# controller-c0m0.net
KiCad netlist of a schematic drawn in EAGLE
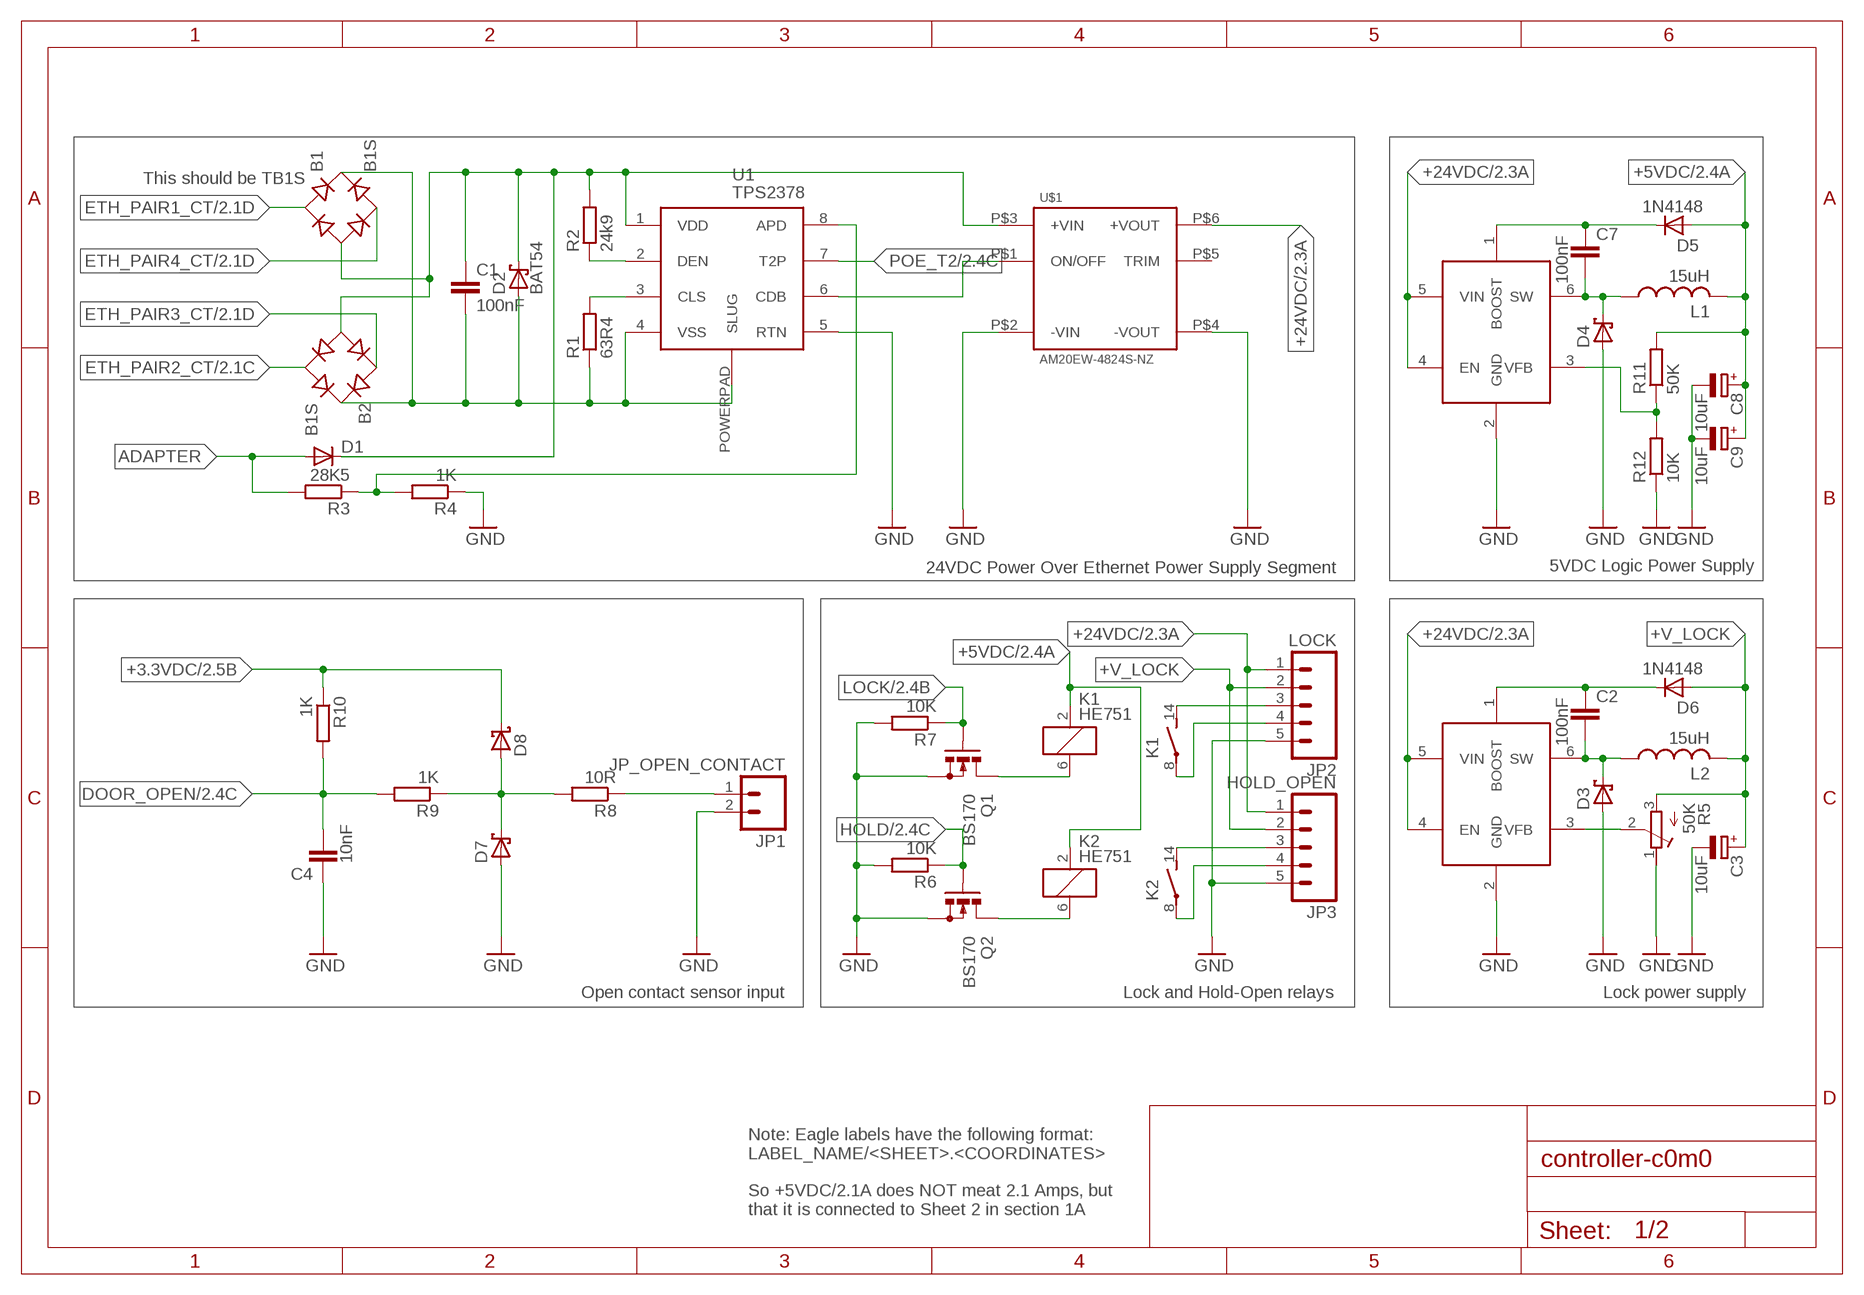
[diagram p0: schematic, sheet 1]
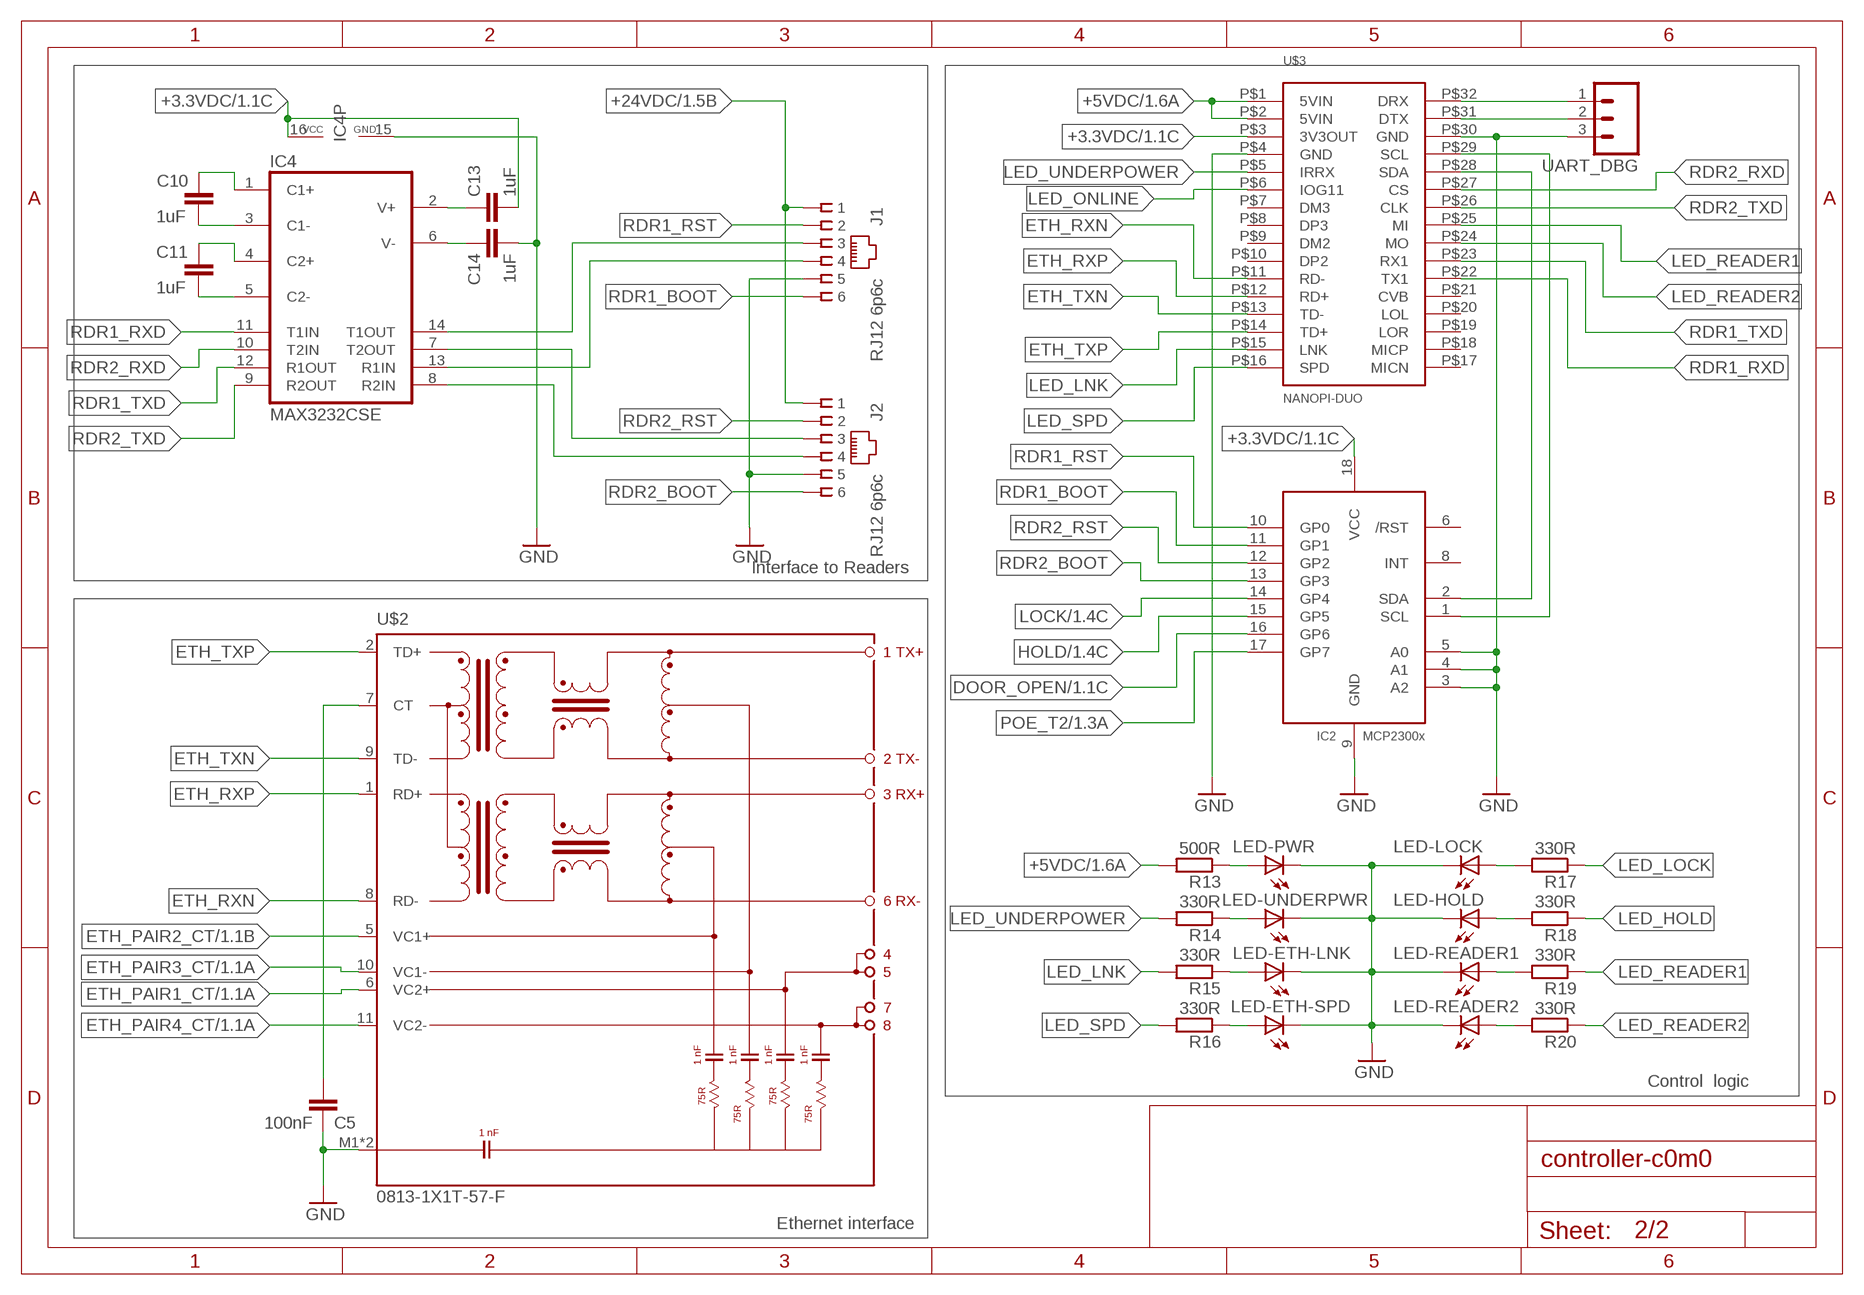
[diagram p1: schematic, sheet 2]

(export (version "E")
  (design (tool "Eeschema 10.0.6"))
  (components
    (comp (ref "C5")
      (value "100nF")
      (footprint "eagle-import:C0805")
      (libsource (lib "eagle-import") (part "C-EUC0805"))
    )
    (comp (ref "C10")
      (value "1uF")
      (footprint "eagle-import:C0805")
      (libsource (lib "eagle-import") (part "C-EUC0805"))
    )
    (comp (ref "C11")
      (value "1uF")
      (footprint "eagle-import:C0805")
      (libsource (lib "eagle-import") (part "C-EUC0805"))
    )
    (comp (ref "C13")
      (value "1uF")
      (footprint "eagle-import:C0805")
      (libsource (lib "eagle-import") (part "C-EUC0805"))
    )
    (comp (ref "C14")
      (value "1uF")
      (footprint "eagle-import:C0805")
      (libsource (lib "eagle-import") (part "C-EUC0805"))
    )
    (comp (ref "IC2")
      (value "MCP23008/SO")
      (footprint "eagle-import:SO18W")
      (libsource (lib "eagle-import") (part "MCP23008/SO"))
    )
    (comp (ref "IC4")
      (value "MAX3232CSE")
      (footprint "eagle-import:SO16")
      (libsource (lib "eagle-import") (part "MAX3232SEC"))
    )
    (comp (ref "J1")
      (value "RJ12 6p6c")
      (footprint "eagle-import:RJ11-NO_SHIELD")
      (libsource (lib "eagle-import") (part "RJ11-2X"))
    )
    (comp (ref "J2")
      (value "RJ12 6p6c")
      (footprint "eagle-import:RJ11-NO_SHIELD")
      (libsource (lib "eagle-import") (part "RJ11-2X"))
    )
    (comp (ref "LED-ETH-LNK")
      (value "LEDCHIP-LED0805")
      (footprint "eagle-import:CHIP-LED0805")
      (libsource (lib "eagle-import") (part "LEDCHIP-LED0805"))
    )
    (comp (ref "LED-ETH-SPD")
      (value "LEDCHIP-LED0805")
      (footprint "eagle-import:CHIP-LED0805")
      (libsource (lib "eagle-import") (part "LEDCHIP-LED0805"))
    )
    (comp (ref "LED-HOLD")
      (value "LEDCHIP-LED0805")
      (footprint "eagle-import:CHIP-LED0805")
      (libsource (lib "eagle-import") (part "LEDCHIP-LED0805"))
    )
    (comp (ref "LED-LOCK")
      (value "LEDCHIP-LED0805")
      (footprint "eagle-import:CHIP-LED0805")
      (libsource (lib "eagle-import") (part "LEDCHIP-LED0805"))
    )
    (comp (ref "LED-PWR")
      (value "LEDCHIP-LED0805")
      (footprint "eagle-import:CHIP-LED0805")
      (libsource (lib "eagle-import") (part "LEDCHIP-LED0805"))
    )
    (comp (ref "LED-READER1")
      (value "LEDCHIP-LED0805")
      (footprint "eagle-import:CHIP-LED0805")
      (libsource (lib "eagle-import") (part "LEDCHIP-LED0805"))
    )
    (comp (ref "LED-READER2")
      (value "LEDCHIP-LED0805")
      (footprint "eagle-import:CHIP-LED0805")
      (libsource (lib "eagle-import") (part "LEDCHIP-LED0805"))
    )
    (comp (ref "LED-UNDERPWR")
      (value "LEDCHIP-LED0805")
      (footprint "eagle-import:CHIP-LED0805")
      (libsource (lib "eagle-import") (part "LEDCHIP-LED0805"))
    )
    (comp (ref "R13")
      (value "500R")
      (footprint "eagle-import:R0805")
      (libsource (lib "eagle-import") (part "R"))
    )
    (comp (ref "R14")
      (value "330R")
      (footprint "eagle-import:R0805")
      (libsource (lib "eagle-import") (part "R"))
    )
    (comp (ref "R15")
      (value "330R")
      (footprint "eagle-import:R0805")
      (libsource (lib "eagle-import") (part "R"))
    )
    (comp (ref "R16")
      (value "330R")
      (footprint "eagle-import:R0805")
      (libsource (lib "eagle-import") (part "R"))
    )
    (comp (ref "R17")
      (value "330R")
      (footprint "eagle-import:R0805")
      (libsource (lib "eagle-import") (part "R"))
    )
    (comp (ref "R18")
      (value "330R")
      (footprint "eagle-import:R0805")
      (libsource (lib "eagle-import") (part "R"))
    )
    (comp (ref "R19")
      (value "330R")
      (footprint "eagle-import:R0805")
      (libsource (lib "eagle-import") (part "R"))
    )
    (comp (ref "R20")
      (value "330R")
      (footprint "eagle-import:R0805")
      (libsource (lib "eagle-import") (part "R"))
    )
    (comp (ref "U$2")
      (value "0813-1X1T-57-F")
      (footprint "eagle-import:J1")
      (libsource (lib "eagle-import") (part "0813-1X1T-57-F"))
    )
    (comp (ref "U$3")
      (value "NANOPI-DUO")
      (footprint "eagle-import:NANOPI-DUO")
      (libsource (lib "eagle-import") (part "NANOPI-DUO"))
    )
    (comp (ref "UART_DBG")
      (value "M03LONGPADS")
      (footprint "eagle-import:1X03_LONGPADS")
      (libsource (lib "eagle-import") (part "M03LONGPADS"))
    )
    (comp (ref "B1")
      (value "B1S")
      (footprint "eagle-import:MBS")
      (libsource (lib "eagle-import") (part "BS1"))
    )
    (comp (ref "B2")
      (value "B1S")
      (footprint "eagle-import:MBS")
      (libsource (lib "eagle-import") (part "BS1"))
    )
    (comp (ref "C1")
      (value "100nF")
      (footprint "eagle-import:C0805")
      (libsource (lib "eagle-import") (part "C"))
    )
    (comp (ref "C2")
      (value "100nF")
      (footprint "eagle-import:C0805")
      (libsource (lib "eagle-import") (part "C-EUC0805"))
    )
    (comp (ref "C3")
      (value "10uF")
      (footprint "eagle-import:A_3216-18R")
      (libsource (lib "eagle-import") (part "CPOL-EUA/3216-18R"))
    )
    (comp (ref "C4")
      (value "10nF")
      (footprint "eagle-import:C0805")
      (libsource (lib "eagle-import") (part "C-EUC0805"))
    )
    (comp (ref "C7")
      (value "100nF")
      (footprint "eagle-import:C0805")
      (libsource (lib "eagle-import") (part "C-EUC0805"))
    )
    (comp (ref "C8")
      (value "10uF")
      (footprint "eagle-import:A_3216-18R")
      (libsource (lib "eagle-import") (part "CPOL-EUA/3216-18R"))
    )
    (comp (ref "C9")
      (value "10uF")
      (footprint "eagle-import:A_3216-18R")
      (libsource (lib "eagle-import") (part "CPOL-EUA/3216-18R"))
    )
    (comp (ref "D1")
      (value "DIODE-SOD323-W")
      (footprint "eagle-import:SOD323-W")
      (libsource (lib "eagle-import") (part "diode_210_DIODE-SOD323-W"))
    )
    (comp (ref "D2")
      (value "BAT54")
      (footprint "eagle-import:SOT23")
      (libsource (lib "eagle-import") (part "BAT54"))
    )
    (comp (ref "D3")
      (value "BAT60J")
      (footprint "eagle-import:SOD323_ST")
      (libsource (lib "eagle-import") (part "BAT60J"))
    )
    (comp (ref "D4")
      (value "BAT60J")
      (footprint "eagle-import:SOD323_ST")
      (libsource (lib "eagle-import") (part "BAT60J"))
    )
    (comp (ref "D5")
      (value "1N4148")
      (footprint "eagle-import:SOD323-W")
      (libsource (lib "eagle-import") (part "DIODE-SOD323-W"))
    )
    (comp (ref "D6")
      (value "1N4148")
      (footprint "eagle-import:SOD323-W")
      (libsource (lib "eagle-import") (part "DIODE-SOD323-W"))
    )
    (comp (ref "D7")
      (value "BAT60J")
      (footprint "eagle-import:SOD323_ST")
      (libsource (lib "eagle-import") (part "BAT60J"))
    )
    (comp (ref "D8")
      (value "BAT60J")
      (footprint "eagle-import:SOD323_ST")
      (libsource (lib "eagle-import") (part "BAT60J"))
    )
    (comp (ref "IC1")
      (value "MCP16301/H")
      (footprint "eagle-import:SOT23-6")
      (libsource (lib "eagle-import") (part "MCP16301/H"))
    )
    (comp (ref "IC3")
      (value "MCP16301/H")
      (footprint "eagle-import:SOT23-6")
      (libsource (lib "eagle-import") (part "MCP16301/H"))
    )
    (comp (ref "JP1")
      (value "JP_OPEN_CONTACT")
      (footprint "eagle-import:1X02_LOCK_LONGPADS")
      (libsource (lib "eagle-import") (part "M02LOCK_LONGPADS"))
    )
    (comp (ref "JP2")
      (value "LOCK")
      (footprint "eagle-import:1X05_LONGPADS")
      (libsource (lib "eagle-import") (part "M05PTH_LONGPADS"))
    )
    (comp (ref "JP3")
      (value "HOLD_OPEN")
      (footprint "eagle-import:1X05_LONGPADS")
      (libsource (lib "eagle-import") (part "M05PTH_LONGPADS"))
    )
    (comp (ref "K1")
      (value "HE751")
      (footprint "eagle-import:HE751")
      (libsource (lib "eagle-import") (part "HE751"))
    )
    (comp (ref "K2")
      (value "HE751")
      (footprint "eagle-import:HE751")
      (libsource (lib "eagle-import") (part "HE751"))
    )
    (comp (ref "L1")
      (value "15uH")
      (footprint "eagle-import:PIS2816")
      (libsource (lib "eagle-import") (part "L-USPIS2816"))
    )
    (comp (ref "L2")
      (value "15uH")
      (footprint "eagle-import:PIS2816")
      (libsource (lib "eagle-import") (part "L-USPIS2816"))
    )
    (comp (ref "Q1")
      (value "BS170")
      (footprint "eagle-import:SOT54E")
      (libsource (lib "eagle-import") (part "BS170"))
    )
    (comp (ref "Q2")
      (value "BS170")
      (footprint "eagle-import:SOT54E")
      (libsource (lib "eagle-import") (part "BS170"))
    )
    (comp (ref "R1")
      (value "63R4")
      (footprint "eagle-import:R0805")
      (libsource (lib "eagle-import") (part "R"))
    )
    (comp (ref "R2")
      (value "24k9")
      (footprint "eagle-import:R0805")
      (libsource (lib "eagle-import") (part "R"))
    )
    (comp (ref "R3")
      (value "28K5")
      (footprint "eagle-import:R0805")
      (libsource (lib "eagle-import") (part "R"))
    )
    (comp (ref "R4")
      (value "1K")
      (footprint "eagle-import:R0805")
      (libsource (lib "eagle-import") (part "R"))
    )
    (comp (ref "R5")
      (value "50K")
      (footprint "eagle-import:RTRIM3314G")
      (libsource (lib "eagle-import") (part "R-TRIMM3314G"))
    )
    (comp (ref "R6")
      (value "10K")
      (footprint "eagle-import:R0805")
      (libsource (lib "eagle-import") (part "R"))
    )
    (comp (ref "R7")
      (value "10K")
      (footprint "eagle-import:R0805")
      (libsource (lib "eagle-import") (part "R"))
    )
    (comp (ref "R8")
      (value "10R")
      (footprint "eagle-import:R0805")
      (libsource (lib "eagle-import") (part "R-EU_R0805"))
    )
    (comp (ref "R9")
      (value "1K")
      (footprint "eagle-import:R0805")
      (libsource (lib "eagle-import") (part "R-EU_R0805"))
    )
    (comp (ref "R10")
      (value "1K")
      (footprint "eagle-import:R0805")
      (libsource (lib "eagle-import") (part "R-EU_R0805"))
    )
    (comp (ref "R11")
      (value "50K")
      (footprint "eagle-import:R0805")
      (libsource (lib "eagle-import") (part "R-EU_R0805"))
    )
    (comp (ref "R12")
      (value "10K")
      (footprint "eagle-import:R0805")
      (libsource (lib "eagle-import") (part "R-EU_R0805"))
    )
    (comp (ref "U$1")
      (value "AM20EW-4824S-NZ")
      (footprint "eagle-import:AM20NW-NZ")
      (libsource (lib "eagle-import") (part "AM20EW-4824S-NZ"))
    )
    (comp (ref "U1")
      (value "TPS2378")
      (footprint "eagle-import:SO08-POWERPAD")
      (libsource (lib "eagle-import") (part "TPS2378"))
    )
  )
  (nets
    (net (code "1") (name "+3.3VDC") (class "Default")
      (node (ref "C13") (pin "2") (pinfunction "2_2") (pintype "passive"))
      (node (ref "D8") (pin "C") (pinfunction "C_C") (pintype "passive"))
      (node (ref "IC2") (pin "18") (pinfunction "VCC_18") (pintype "power_in"))
      (node (ref "IC4") (pin "16") (pinfunction "VCC_16") (pintype "power_in"))
      (node (ref "R10") (pin "1") (pinfunction "1_1") (pintype "passive"))
      (node (ref "U$3") (pin "P$3") (pinfunction "3V3OUT_P$3") (pintype "power_in"))
    )
    (net (code "2") (name "+5VDC") (class "Default")
      (node (ref "C8") (pin "+") (pinfunction "+_+") (pintype "passive"))
      (node (ref "C9") (pin "+") (pinfunction "+_+") (pintype "passive"))
      (node (ref "D5") (pin "A") (pinfunction "A_A") (pintype "passive"))
      (node (ref "K1") (pin "2") (pinfunction "1_2") (pintype "passive"))
      (node (ref "K2") (pin "2") (pinfunction "1_2") (pintype "passive"))
      (node (ref "L1") (pin "2") (pinfunction "2_2") (pintype "passive"))
      (node (ref "R11") (pin "2") (pinfunction "2_2") (pintype "passive"))
      (node (ref "R13") (pin "2") (pinfunction "2_2") (pintype "passive"))
      (node (ref "U$3") (pin "P$1") (pinfunction "5VIN_P$1") (pintype "power_in"))
      (node (ref "U$3") (pin "P$2") (pinfunction "5VIN_P$2") (pintype "power_in"))
    )
    (net (code "3") (name "+24VDC") (class "Default")
      (node (ref "IC1") (pin "4") (pinfunction "EN_4") (pintype "bidirectional"))
      (node (ref "IC1") (pin "5") (pinfunction "VIN_5") (pintype "power_in"))
      (node (ref "IC3") (pin "4") (pinfunction "EN_4") (pintype "bidirectional"))
      (node (ref "IC3") (pin "5") (pinfunction "VIN_5") (pintype "power_in"))
      (node (ref "J1") (pin "1") (pinfunction "1_1") (pintype "passive"))
      (node (ref "J2") (pin "1") (pinfunction "1_1") (pintype "passive"))
      (node (ref "JP2") (pin "1") (pinfunction "1_1") (pintype "passive"))
      (node (ref "JP3") (pin "1") (pinfunction "1_1") (pintype "passive"))
      (node (ref "U$1") (pin "P$6") (pinfunction "+VOUT_P$6") (pintype "power_in"))
    )
    (net (code "4") (name "+V_LOCK") (class "Default")
      (node (ref "C3") (pin "+") (pinfunction "+_+") (pintype "passive"))
      (node (ref "D6") (pin "A") (pinfunction "A_A") (pintype "passive"))
      (node (ref "JP2") (pin "2") (pinfunction "2_2") (pintype "passive"))
      (node (ref "JP3") (pin "2") (pinfunction "2_2") (pintype "passive"))
      (node (ref "L2") (pin "2") (pinfunction "2_2") (pintype "passive"))
      (node (ref "R5") (pin "3") (pinfunction "A_3") (pintype "passive"))
    )
    (net (code "5") (name "ADAPTER") (class "Default")
      (node (ref "D1") (pin "A") (pinfunction "A_A") (pintype "passive"))
      (node (ref "R3") (pin "2") (pinfunction "2_2") (pintype "passive"))
    )
    (net (code "6") (name "DOOR_OPEN") (class "Default")
      (node (ref "C4") (pin "2") (pinfunction "2_2") (pintype "passive"))
      (node (ref "IC2") (pin "16") (pinfunction "GP6_16") (pintype "bidirectional"))
      (node (ref "R10") (pin "2") (pinfunction "2_2") (pintype "passive"))
      (node (ref "R9") (pin "2") (pinfunction "2_2") (pintype "passive"))
    )
    (net (code "7") (name "ETH_PAIR1_CT") (class "Default")
      (node (ref "B1") (pin "AC1") (pinfunction "AC1_AC1") (pintype "passive"))
      (node (ref "U$2") (pin "6") (pinfunction "VC2+_6") (pintype "input"))
    )
    (net (code "8") (name "ETH_PAIR2_CT") (class "Default")
      (node (ref "B2") (pin "AC2") (pinfunction "AC2_AC2") (pintype "passive"))
      (node (ref "U$2") (pin "5") (pinfunction "VC1+_5") (pintype "input"))
    )
    (net (code "9") (name "ETH_PAIR3_CT") (class "Default")
      (node (ref "B2") (pin "AC1") (pinfunction "AC1_AC1") (pintype "passive"))
      (node (ref "U$2") (pin "10") (pinfunction "VC1-_10") (pintype "input"))
    )
    (net (code "10") (name "ETH_PAIR4_CT") (class "Default")
      (node (ref "B1") (pin "AC2") (pinfunction "AC2_AC2") (pintype "passive"))
      (node (ref "U$2") (pin "11") (pinfunction "VC2-_11") (pintype "input"))
    )
    (net (code "11") (name "ETH_RXN") (class "Default")
      (node (ref "U$2") (pin "8") (pinfunction "RD-_8") (pintype "input"))
      (node (ref "U$3") (pin "P$11") (pinfunction "RD-_P$11") (pintype "bidirectional"))
    )
    (net (code "12") (name "ETH_RXP") (class "Default")
      (node (ref "U$2") (pin "1") (pinfunction "RD+_1") (pintype "input"))
      (node (ref "U$3") (pin "P$12") (pinfunction "RD+_P$12") (pintype "bidirectional"))
    )
    (net (code "13") (name "ETH_TXN") (class "Default")
      (node (ref "U$2") (pin "9") (pinfunction "TD-_9") (pintype "input"))
      (node (ref "U$3") (pin "P$13") (pinfunction "TD-_P$13") (pintype "bidirectional"))
    )
    (net (code "14") (name "ETH_TXP") (class "Default")
      (node (ref "U$2") (pin "2") (pinfunction "TD+_2") (pintype "input"))
      (node (ref "U$3") (pin "P$14") (pinfunction "TD+_P$14") (pintype "bidirectional"))
    )
    (net (code "15") (name "GND") (class "Default")
      (node (ref "C14") (pin "2") (pinfunction "2_2") (pintype "passive"))
      (node (ref "C3") (pin "-") (pinfunction "-_-") (pintype "passive"))
      (node (ref "C4") (pin "1") (pinfunction "1_1") (pintype "passive"))
      (node (ref "C5") (pin "1") (pinfunction "1_1") (pintype "passive"))
      (node (ref "C8") (pin "-") (pinfunction "-_-") (pintype "passive"))
      (node (ref "C9") (pin "-") (pinfunction "-_-") (pintype "passive"))
      (node (ref "D3") (pin "A") (pinfunction "A_A") (pintype "passive"))
      (node (ref "D4") (pin "A") (pinfunction "A_A") (pintype "passive"))
      (node (ref "D7") (pin "A") (pinfunction "A_A") (pintype "passive"))
      (node (ref "IC1") (pin "2") (pinfunction "GND_2") (pintype "power_in"))
      (node (ref "IC2") (pin "3") (pinfunction "A2_3") (pintype "input"))
      (node (ref "IC2") (pin "4") (pinfunction "A1_4") (pintype "input"))
      (node (ref "IC2") (pin "5") (pinfunction "A0_5") (pintype "input"))
      (node (ref "IC2") (pin "9") (pinfunction "GND_9") (pintype "power_in"))
      (node (ref "IC3") (pin "2") (pinfunction "GND_2") (pintype "power_in"))
      (node (ref "IC4") (pin "15") (pinfunction "GND_15") (pintype "power_in"))
      (node (ref "J1") (pin "5") (pinfunction "5_5") (pintype "passive"))
      (node (ref "J2") (pin "5") (pinfunction "5_5") (pintype "passive"))
      (node (ref "JP1") (pin "2") (pinfunction "2_2") (pintype "passive"))
      (node (ref "JP2") (pin "5") (pinfunction "5_5") (pintype "passive"))
      (node (ref "JP3") (pin "5") (pinfunction "5_5") (pintype "passive"))
      (node (ref "LED-ETH-LNK") (pin "C") (pinfunction "C_C") (pintype "passive"))
      (node (ref "LED-ETH-SPD") (pin "C") (pinfunction "C_C") (pintype "passive"))
      (node (ref "LED-HOLD") (pin "C") (pinfunction "C_C") (pintype "passive"))
      (node (ref "LED-LOCK") (pin "C") (pinfunction "C_C") (pintype "passive"))
      (node (ref "LED-PWR") (pin "C") (pinfunction "C_C") (pintype "passive"))
      (node (ref "LED-READER1") (pin "C") (pinfunction "C_C") (pintype "passive"))
      (node (ref "LED-READER2") (pin "C") (pinfunction "C_C") (pintype "passive"))
      (node (ref "LED-UNDERPWR") (pin "C") (pinfunction "C_C") (pintype "passive"))
      (node (ref "Q1") (pin "S") (pinfunction "S_S") (pintype "passive"))
      (node (ref "Q2") (pin "S") (pinfunction "S_S") (pintype "passive"))
      (node (ref "R12") (pin "1") (pinfunction "1_1") (pintype "passive"))
      (node (ref "R4") (pin "1") (pinfunction "1_1") (pintype "passive"))
      (node (ref "R5") (pin "1") (pinfunction "E_1") (pintype "passive"))
      (node (ref "R6") (pin "2") (pinfunction "2_2") (pintype "passive"))
      (node (ref "R7") (pin "2") (pinfunction "2_2") (pintype "passive"))
      (node (ref "U$1") (pin "P$2") (pinfunction "-VIN_P$2") (pintype "power_in"))
      (node (ref "U$1") (pin "P$4") (pinfunction "-VOUT_P$4") (pintype "power_in"))
      (node (ref "U$2") (pin "M1") (pinfunction "5_M1") (pintype "input"))
      (node (ref "U$2") (pin "M2") (pinfunction "5_M2") (pintype "input"))
      (node (ref "U$3") (pin "P$30") (pinfunction "GND_P$30") (pintype "power_in"))
      (node (ref "U$3") (pin "P$4") (pinfunction "GND_P$4") (pintype "power_in"))
      (node (ref "U1") (pin "5") (pinfunction "RTN_5") (pintype "power_in"))
      (node (ref "UART_DBG") (pin "3") (pinfunction "3_3") (pintype "passive"))
    )
    (net (code "16") (name "HOLD") (class "Default")
      (node (ref "IC2") (pin "15") (pinfunction "GP5_15") (pintype "bidirectional"))
      (node (ref "Q2") (pin "G") (pinfunction "G_G") (pintype "passive"))
      (node (ref "R6") (pin "1") (pinfunction "1_1") (pintype "passive"))
    )
    (net (code "17") (name "LED_HOLD") (class "Default")
      (node (ref "R18") (pin "1") (pinfunction "1_1") (pintype "passive"))
    )
    (net (code "18") (name "LED_LNK") (class "Default")
      (node (ref "R15") (pin "2") (pinfunction "2_2") (pintype "passive"))
      (node (ref "U$3") (pin "P$15") (pinfunction "LNK_P$15") (pintype "output"))
    )
    (net (code "19") (name "LED_LOCK") (class "Default")
      (node (ref "R17") (pin "1") (pinfunction "1_1") (pintype "passive"))
    )
    (net (code "20") (name "LED_ONLINE") (class "Default")
      (node (ref "U$3") (pin "P$6") (pinfunction "IOG11_P$6") (pintype "bidirectional"))
    )
    (net (code "21") (name "LED_READER1") (class "Default")
      (node (ref "R19") (pin "1") (pinfunction "1_1") (pintype "passive"))
      (node (ref "U$3") (pin "P$25") (pinfunction "MI_P$25") (pintype "bidirectional"))
    )
    (net (code "22") (name "LED_READER2") (class "Default")
      (node (ref "R20") (pin "1") (pinfunction "1_1") (pintype "passive"))
      (node (ref "U$3") (pin "P$24") (pinfunction "MO_P$24") (pintype "bidirectional"))
    )
    (net (code "23") (name "LED_SPD") (class "Default")
      (node (ref "R16") (pin "2") (pinfunction "2_2") (pintype "passive"))
      (node (ref "U$3") (pin "P$16") (pinfunction "SPD_P$16") (pintype "output"))
    )
    (net (code "24") (name "LED_UNDERPOWER") (class "Default")
      (node (ref "R14") (pin "2") (pinfunction "2_2") (pintype "passive"))
      (node (ref "U$3") (pin "P$5") (pinfunction "IRRX_P$5") (pintype "bidirectional"))
    )
    (net (code "25") (name "LOCK") (class "Default")
      (node (ref "IC2") (pin "14") (pinfunction "GP4_14") (pintype "bidirectional"))
      (node (ref "Q1") (pin "G") (pinfunction "G_G") (pintype "passive"))
      (node (ref "R7") (pin "1") (pinfunction "1_1") (pintype "passive"))
    )
    (net (code "26") (name "Net-(D2-A)") (class "Default")
      (node (ref "B1") (pin "+") (pinfunction "+_+") (pintype "passive"))
      (node (ref "B2") (pin "+") (pinfunction "+_+") (pintype "passive"))
      (node (ref "C1") (pin "2") (pinfunction "2_2") (pintype "passive"))
      (node (ref "D2") (pin "1") (pinfunction "A_1") (pintype "passive"))
      (node (ref "R1") (pin "1") (pinfunction "1_1") (pintype "passive"))
      (node (ref "U1") (pin "4") (pinfunction "VSS_4") (pintype "power_in"))
      (node (ref "U1") (pin "POWERPAD") (pinfunction "SLUG_POWERPAD") (pintype "power_in"))
    )
    (net (code "27") (name "Net-(D2-C)") (class "Default")
      (node (ref "B1") (pin "-") (pinfunction "-_-") (pintype "passive"))
      (node (ref "B2") (pin "-") (pinfunction "-_-") (pintype "passive"))
      (node (ref "C1") (pin "1") (pinfunction "1_1") (pintype "passive"))
      (node (ref "D1") (pin "C") (pinfunction "C_C") (pintype "passive"))
      (node (ref "D2") (pin "3") (pinfunction "C_3") (pintype "passive"))
      (node (ref "R2") (pin "2") (pinfunction "2_2") (pintype "passive"))
      (node (ref "U$1") (pin "P$3") (pinfunction "+VIN_P$3") (pintype "power_in"))
      (node (ref "U1") (pin "1") (pinfunction "VDD_1") (pintype "input"))
    )
    (net (code "28") (name "Net-(D7-PadC)") (class "Default")
      (node (ref "D7") (pin "C") (pinfunction "C_C") (pintype "passive"))
      (node (ref "D8") (pin "A") (pinfunction "A_A") (pintype "passive"))
      (node (ref "R8") (pin "2") (pinfunction "2_2") (pintype "passive"))
      (node (ref "R9") (pin "1") (pinfunction "1_1") (pintype "passive"))
    )
    (net (code "29") (name "Net-(IC1-BOOST)") (class "Default")
      (node (ref "C2") (pin "1") (pinfunction "1_1") (pintype "passive"))
      (node (ref "D6") (pin "C") (pinfunction "C_C") (pintype "passive"))
      (node (ref "IC1") (pin "1") (pinfunction "BOOST_1") (pintype "bidirectional"))
    )
    (net (code "30") (name "Net-(IC1-SW)") (class "Default")
      (node (ref "C2") (pin "2") (pinfunction "2_2") (pintype "passive"))
      (node (ref "D3") (pin "C") (pinfunction "C_C") (pintype "passive"))
      (node (ref "IC1") (pin "6") (pinfunction "SW_6") (pintype "power_in"))
      (node (ref "L2") (pin "1") (pinfunction "1_1") (pintype "passive"))
    )
    (net (code "31") (name "Net-(IC1-VFB)") (class "Default")
      (node (ref "IC1") (pin "3") (pinfunction "VFB_3") (pintype "bidirectional"))
      (node (ref "R5") (pin "2") (pinfunction "S_2") (pintype "passive"))
    )
    (net (code "32") (name "Net-(IC2-SCL)") (class "Default")
      (node (ref "IC2") (pin "1") (pinfunction "SCL_1") (pintype "bidirectional"))
      (node (ref "U$3") (pin "P$29") (pinfunction "SCL_P$29") (pintype "bidirectional"))
    )
    (net (code "33") (name "Net-(IC2-SDA)") (class "Default")
      (node (ref "IC2") (pin "2") (pinfunction "SDA_2") (pintype "bidirectional"))
      (node (ref "U$3") (pin "P$28") (pinfunction "SDA_P$28") (pintype "bidirectional"))
    )
    (net (code "34") (name "Net-(IC3-BOOST)") (class "Default")
      (node (ref "C7") (pin "1") (pinfunction "1_1") (pintype "passive"))
      (node (ref "D5") (pin "C") (pinfunction "C_C") (pintype "passive"))
      (node (ref "IC3") (pin "1") (pinfunction "BOOST_1") (pintype "bidirectional"))
    )
    (net (code "35") (name "Net-(IC3-SW)") (class "Default")
      (node (ref "C7") (pin "2") (pinfunction "2_2") (pintype "passive"))
      (node (ref "D4") (pin "C") (pinfunction "C_C") (pintype "passive"))
      (node (ref "IC3") (pin "6") (pinfunction "SW_6") (pintype "power_in"))
      (node (ref "L1") (pin "1") (pinfunction "1_1") (pintype "passive"))
    )
    (net (code "36") (name "Net-(IC3-VFB)") (class "Default")
      (node (ref "IC3") (pin "3") (pinfunction "VFB_3") (pintype "bidirectional"))
      (node (ref "R11") (pin "1") (pinfunction "1_1") (pintype "passive"))
      (node (ref "R12") (pin "2") (pinfunction "2_2") (pintype "passive"))
    )
    (net (code "37") (name "Net-(IC4A-C1+)") (class "Default")
      (node (ref "C10") (pin "1") (pinfunction "1_1") (pintype "passive"))
      (node (ref "IC4") (pin "1") (pinfunction "C1+_1") (pintype "bidirectional"))
    )
    (net (code "38") (name "Net-(IC4A-C1-)") (class "Default")
      (node (ref "C10") (pin "2") (pinfunction "2_2") (pintype "passive"))
      (node (ref "IC4") (pin "3") (pinfunction "C1-_3") (pintype "bidirectional"))
    )
    (net (code "39") (name "Net-(IC4A-C2+)") (class "Default")
      (node (ref "C11") (pin "1") (pinfunction "1_1") (pintype "passive"))
      (node (ref "IC4") (pin "4") (pinfunction "C2+_4") (pintype "bidirectional"))
    )
    (net (code "40") (name "Net-(IC4A-C2-)") (class "Default")
      (node (ref "C11") (pin "2") (pinfunction "2_2") (pintype "passive"))
      (node (ref "IC4") (pin "5") (pinfunction "C2-_5") (pintype "bidirectional"))
    )
    (net (code "41") (name "Net-(IC4A-R1IN)") (class "Default")
      (node (ref "IC4") (pin "13") (pinfunction "R1IN_13") (pintype "input"))
      (node (ref "J1") (pin "4") (pinfunction "4_4") (pintype "passive"))
    )
    (net (code "42") (name "Net-(IC4A-R2IN)") (class "Default")
      (node (ref "IC4") (pin "8") (pinfunction "R2IN_8") (pintype "input"))
      (node (ref "J2") (pin "4") (pinfunction "4_4") (pintype "passive"))
    )
    (net (code "43") (name "Net-(IC4A-T1OUT)") (class "Default")
      (node (ref "IC4") (pin "14") (pinfunction "T1OUT_14") (pintype "output"))
      (node (ref "J1") (pin "3") (pinfunction "3_3") (pintype "passive"))
    )
    (net (code "44") (name "Net-(IC4A-T2OUT)") (class "Default")
      (node (ref "IC4") (pin "7") (pinfunction "T2OUT_7") (pintype "output"))
      (node (ref "J2") (pin "3") (pinfunction "3_3") (pintype "passive"))
    )
    (net (code "45") (name "Net-(IC4A-V+)") (class "Default")
      (node (ref "C13") (pin "1") (pinfunction "1_1") (pintype "passive"))
      (node (ref "IC4") (pin "2") (pinfunction "V+_2") (pintype "bidirectional"))
    )
    (net (code "46") (name "Net-(IC4A-V-)") (class "Default")
      (node (ref "C14") (pin "1") (pinfunction "1_1") (pintype "passive"))
      (node (ref "IC4") (pin "6") (pinfunction "V-_6") (pintype "bidirectional"))
    )
    (net (code "47") (name "Net-(JP1-Pad1)") (class "Default")
      (node (ref "JP1") (pin "1") (pinfunction "1_1") (pintype "passive"))
      (node (ref "R8") (pin "1") (pinfunction "1_1") (pintype "passive"))
    )
    (net (code "48") (name "Net-(K1A-2)") (class "Default")
      (node (ref "K1") (pin "6") (pinfunction "2_6") (pintype "passive"))
      (node (ref "Q1") (pin "D") (pinfunction "D_D") (pintype "passive"))
    )
    (net (code "49") (name "Net-(K1B-P)") (class "Default")
      (node (ref "JP2") (pin "4") (pinfunction "4_4") (pintype "passive"))
      (node (ref "K1") (pin "8") (pinfunction "P_8") (pintype "passive"))
    )
    (net (code "50") (name "Net-(K1B-S)") (class "Default")
      (node (ref "JP2") (pin "3") (pinfunction "3_3") (pintype "passive"))
      (node (ref "K1") (pin "14") (pinfunction "S_14") (pintype "passive"))
    )
    (net (code "51") (name "Net-(K2A-2)") (class "Default")
      (node (ref "K2") (pin "6") (pinfunction "2_6") (pintype "passive"))
      (node (ref "Q2") (pin "D") (pinfunction "D_D") (pintype "passive"))
    )
    (net (code "52") (name "Net-(K2B-P)") (class "Default")
      (node (ref "JP3") (pin "4") (pinfunction "4_4") (pintype "passive"))
      (node (ref "K2") (pin "8") (pinfunction "P_8") (pintype "passive"))
    )
    (net (code "53") (name "Net-(K2B-S)") (class "Default")
      (node (ref "JP3") (pin "3") (pinfunction "3_3") (pintype "passive"))
      (node (ref "K2") (pin "14") (pinfunction "S_14") (pintype "passive"))
    )
    (net (code "54") (name "Net-(LED-ETH-LNK-PadA)") (class "Default")
      (node (ref "LED-ETH-LNK") (pin "A") (pinfunction "A_A") (pintype "passive"))
      (node (ref "R15") (pin "1") (pinfunction "1_1") (pintype "passive"))
    )
    (net (code "55") (name "Net-(LED-ETH-SPD-PadA)") (class "Default")
      (node (ref "LED-ETH-SPD") (pin "A") (pinfunction "A_A") (pintype "passive"))
      (node (ref "R16") (pin "1") (pinfunction "1_1") (pintype "passive"))
    )
    (net (code "56") (name "Net-(LED-HOLD-PadA)") (class "Default")
      (node (ref "LED-HOLD") (pin "A") (pinfunction "A_A") (pintype "passive"))
      (node (ref "R18") (pin "2") (pinfunction "2_2") (pintype "passive"))
    )
    (net (code "57") (name "Net-(LED-LOCK-PadA)") (class "Default")
      (node (ref "LED-LOCK") (pin "A") (pinfunction "A_A") (pintype "passive"))
      (node (ref "R17") (pin "2") (pinfunction "2_2") (pintype "passive"))
    )
    (net (code "58") (name "Net-(LED-PWR-PadA)") (class "Default")
      (node (ref "LED-PWR") (pin "A") (pinfunction "A_A") (pintype "passive"))
      (node (ref "R13") (pin "1") (pinfunction "1_1") (pintype "passive"))
    )
    (net (code "59") (name "Net-(LED-READER1-PadA)") (class "Default")
      (node (ref "LED-READER1") (pin "A") (pinfunction "A_A") (pintype "passive"))
      (node (ref "R19") (pin "2") (pinfunction "2_2") (pintype "passive"))
    )
    (net (code "60") (name "Net-(LED-READER2-PadA)") (class "Default")
      (node (ref "LED-READER2") (pin "A") (pinfunction "A_A") (pintype "passive"))
      (node (ref "R20") (pin "2") (pinfunction "2_2") (pintype "passive"))
    )
    (net (code "61") (name "Net-(LED-UNDERPWR-PadA)") (class "Default")
      (node (ref "LED-UNDERPWR") (pin "A") (pinfunction "A_A") (pintype "passive"))
      (node (ref "R14") (pin "1") (pinfunction "1_1") (pintype "passive"))
    )
    (net (code "62") (name "Net-(U$1-ON{slash}OFF)") (class "Default")
      (node (ref "U$1") (pin "P$1") (pinfunction "ON/OFF_P$1") (pintype "input"))
      (node (ref "U1") (pin "6") (pinfunction "CDB_6") (pintype "output"))
    )
    (net (code "63") (name "Net-(U$2-CT)") (class "Default")
      (node (ref "C5") (pin "2") (pinfunction "2_2") (pintype "passive"))
      (node (ref "U$2") (pin "7") (pinfunction "CT_7") (pintype "input"))
    )
    (net (code "64") (name "Net-(U$3-DRX)") (class "Default")
      (node (ref "U$3") (pin "P$32") (pinfunction "DRX_P$32") (pintype "bidirectional"))
      (node (ref "UART_DBG") (pin "1") (pinfunction "1_1") (pintype "passive"))
    )
    (net (code "65") (name "Net-(U$3-DTX)") (class "Default")
      (node (ref "U$3") (pin "P$31") (pinfunction "DTX_P$31") (pintype "bidirectional"))
      (node (ref "UART_DBG") (pin "2") (pinfunction "2_2") (pintype "passive"))
    )
    (net (code "66") (name "Net-(U1-APD)") (class "Default")
      (node (ref "R3") (pin "1") (pinfunction "1_1") (pintype "passive"))
      (node (ref "R4") (pin "2") (pinfunction "2_2") (pintype "passive"))
      (node (ref "U1") (pin "8") (pinfunction "APD_8") (pintype "input"))
    )
    (net (code "67") (name "Net-(U1-CLS)") (class "Default")
      (node (ref "R1") (pin "2") (pinfunction "2_2") (pintype "passive"))
      (node (ref "U1") (pin "3") (pinfunction "CLS_3") (pintype "output"))
    )
    (net (code "68") (name "Net-(U1-DEN)") (class "Default")
      (node (ref "R2") (pin "1") (pinfunction "1_1") (pintype "passive"))
      (node (ref "U1") (pin "2") (pinfunction "DEN_2") (pintype "bidirectional"))
    )
    (net (code "69") (name "POE_T2") (class "Default")
      (node (ref "IC2") (pin "17") (pinfunction "GP7_17") (pintype "bidirectional"))
      (node (ref "U1") (pin "7") (pinfunction "T2P_7") (pintype "output"))
    )
    (net (code "70") (name "RDR1_BOOT") (class "Default")
      (node (ref "IC2") (pin "11") (pinfunction "GP1_11") (pintype "bidirectional"))
      (node (ref "J1") (pin "6") (pinfunction "6_6") (pintype "passive"))
    )
    (net (code "71") (name "RDR1_RST") (class "Default")
      (node (ref "IC2") (pin "10") (pinfunction "GP0_10") (pintype "bidirectional"))
      (node (ref "J1") (pin "2") (pinfunction "2_2") (pintype "passive"))
    )
    (net (code "72") (name "RDR1_RXD") (class "Default")
      (node (ref "IC4") (pin "11") (pinfunction "T1IN_11") (pintype "input"))
      (node (ref "U$3") (pin "P$22") (pinfunction "TX1_P$22") (pintype "bidirectional"))
    )
    (net (code "73") (name "RDR1_TXD") (class "Default")
      (node (ref "IC4") (pin "12") (pinfunction "R1OUT_12") (pintype "output"))
      (node (ref "U$3") (pin "P$23") (pinfunction "RX1_P$23") (pintype "bidirectional"))
    )
    (net (code "74") (name "RDR2_BOOT") (class "Default")
      (node (ref "IC2") (pin "13") (pinfunction "GP3_13") (pintype "bidirectional"))
      (node (ref "J2") (pin "6") (pinfunction "6_6") (pintype "passive"))
    )
    (net (code "75") (name "RDR2_RST") (class "Default")
      (node (ref "IC2") (pin "12") (pinfunction "GP2_12") (pintype "bidirectional"))
      (node (ref "J2") (pin "2") (pinfunction "2_2") (pintype "passive"))
    )
    (net (code "76") (name "RDR2_RXD") (class "Default")
      (node (ref "IC4") (pin "10") (pinfunction "T2IN_10") (pintype "input"))
      (node (ref "U$3") (pin "P$27") (pinfunction "CS_P$27") (pintype "bidirectional"))
    )
    (net (code "77") (name "RDR2_TXD") (class "Default")
      (node (ref "IC4") (pin "9") (pinfunction "R2OUT_9") (pintype "output"))
      (node (ref "U$3") (pin "P$26") (pinfunction "CLK_P$26") (pintype "bidirectional"))
    )
    (net (code "78") (name "unconnected-(IC2-INT-Pad8)") (class "Default")
      (node (ref "IC2") (pin "8") (pinfunction "INT_8") (pintype "output"))
    )
    (net (code "79") (name "unconnected-(IC2-{slash}RST-Pad6)") (class "Default")
      (node (ref "IC2") (pin "6") (pinfunction "/RST_6") (pintype "input"))
    )
    (net (code "80") (name "unconnected-(U$1-TRIM-PadP$5)") (class "Default")
      (node (ref "U$1") (pin "P$5") (pinfunction "TRIM_P$5") (pintype "bidirectional"))
    )
    (net (code "81") (name "unconnected-(U$3-CVB-PadP$21)") (class "Default")
      (node (ref "U$3") (pin "P$21") (pinfunction "CVB_P$21") (pintype "bidirectional"))
    )
    (net (code "82") (name "unconnected-(U$3-DM2-PadP$9)") (class "Default")
      (node (ref "U$3") (pin "P$9") (pinfunction "DM2_P$9") (pintype "bidirectional"))
    )
    (net (code "83") (name "unconnected-(U$3-DM3-PadP$7)") (class "Default")
      (node (ref "U$3") (pin "P$7") (pinfunction "DM3_P$7") (pintype "bidirectional"))
    )
    (net (code "84") (name "unconnected-(U$3-DP2-PadP$10)") (class "Default")
      (node (ref "U$3") (pin "P$10") (pinfunction "DP2_P$10") (pintype "bidirectional"))
    )
    (net (code "85") (name "unconnected-(U$3-DP3-PadP$8)") (class "Default")
      (node (ref "U$3") (pin "P$8") (pinfunction "DP3_P$8") (pintype "bidirectional"))
    )
    (net (code "86") (name "unconnected-(U$3-LOL-PadP$20)") (class "Default")
      (node (ref "U$3") (pin "P$20") (pinfunction "LOL_P$20") (pintype "bidirectional"))
    )
    (net (code "87") (name "unconnected-(U$3-LOR-PadP$19)") (class "Default")
      (node (ref "U$3") (pin "P$19") (pinfunction "LOR_P$19") (pintype "bidirectional"))
    )
    (net (code "88") (name "unconnected-(U$3-MICN-PadP$17)") (class "Default")
      (node (ref "U$3") (pin "P$17") (pinfunction "MICN_P$17") (pintype "bidirectional"))
    )
    (net (code "89") (name "unconnected-(U$3-MICP-PadP$18)") (class "Default")
      (node (ref "U$3") (pin "P$18") (pinfunction "MICP_P$18") (pintype "bidirectional"))
    )
  )
)
